# fhd-hdr.net
KiCad netlist of a schematic drawn in EAGLE
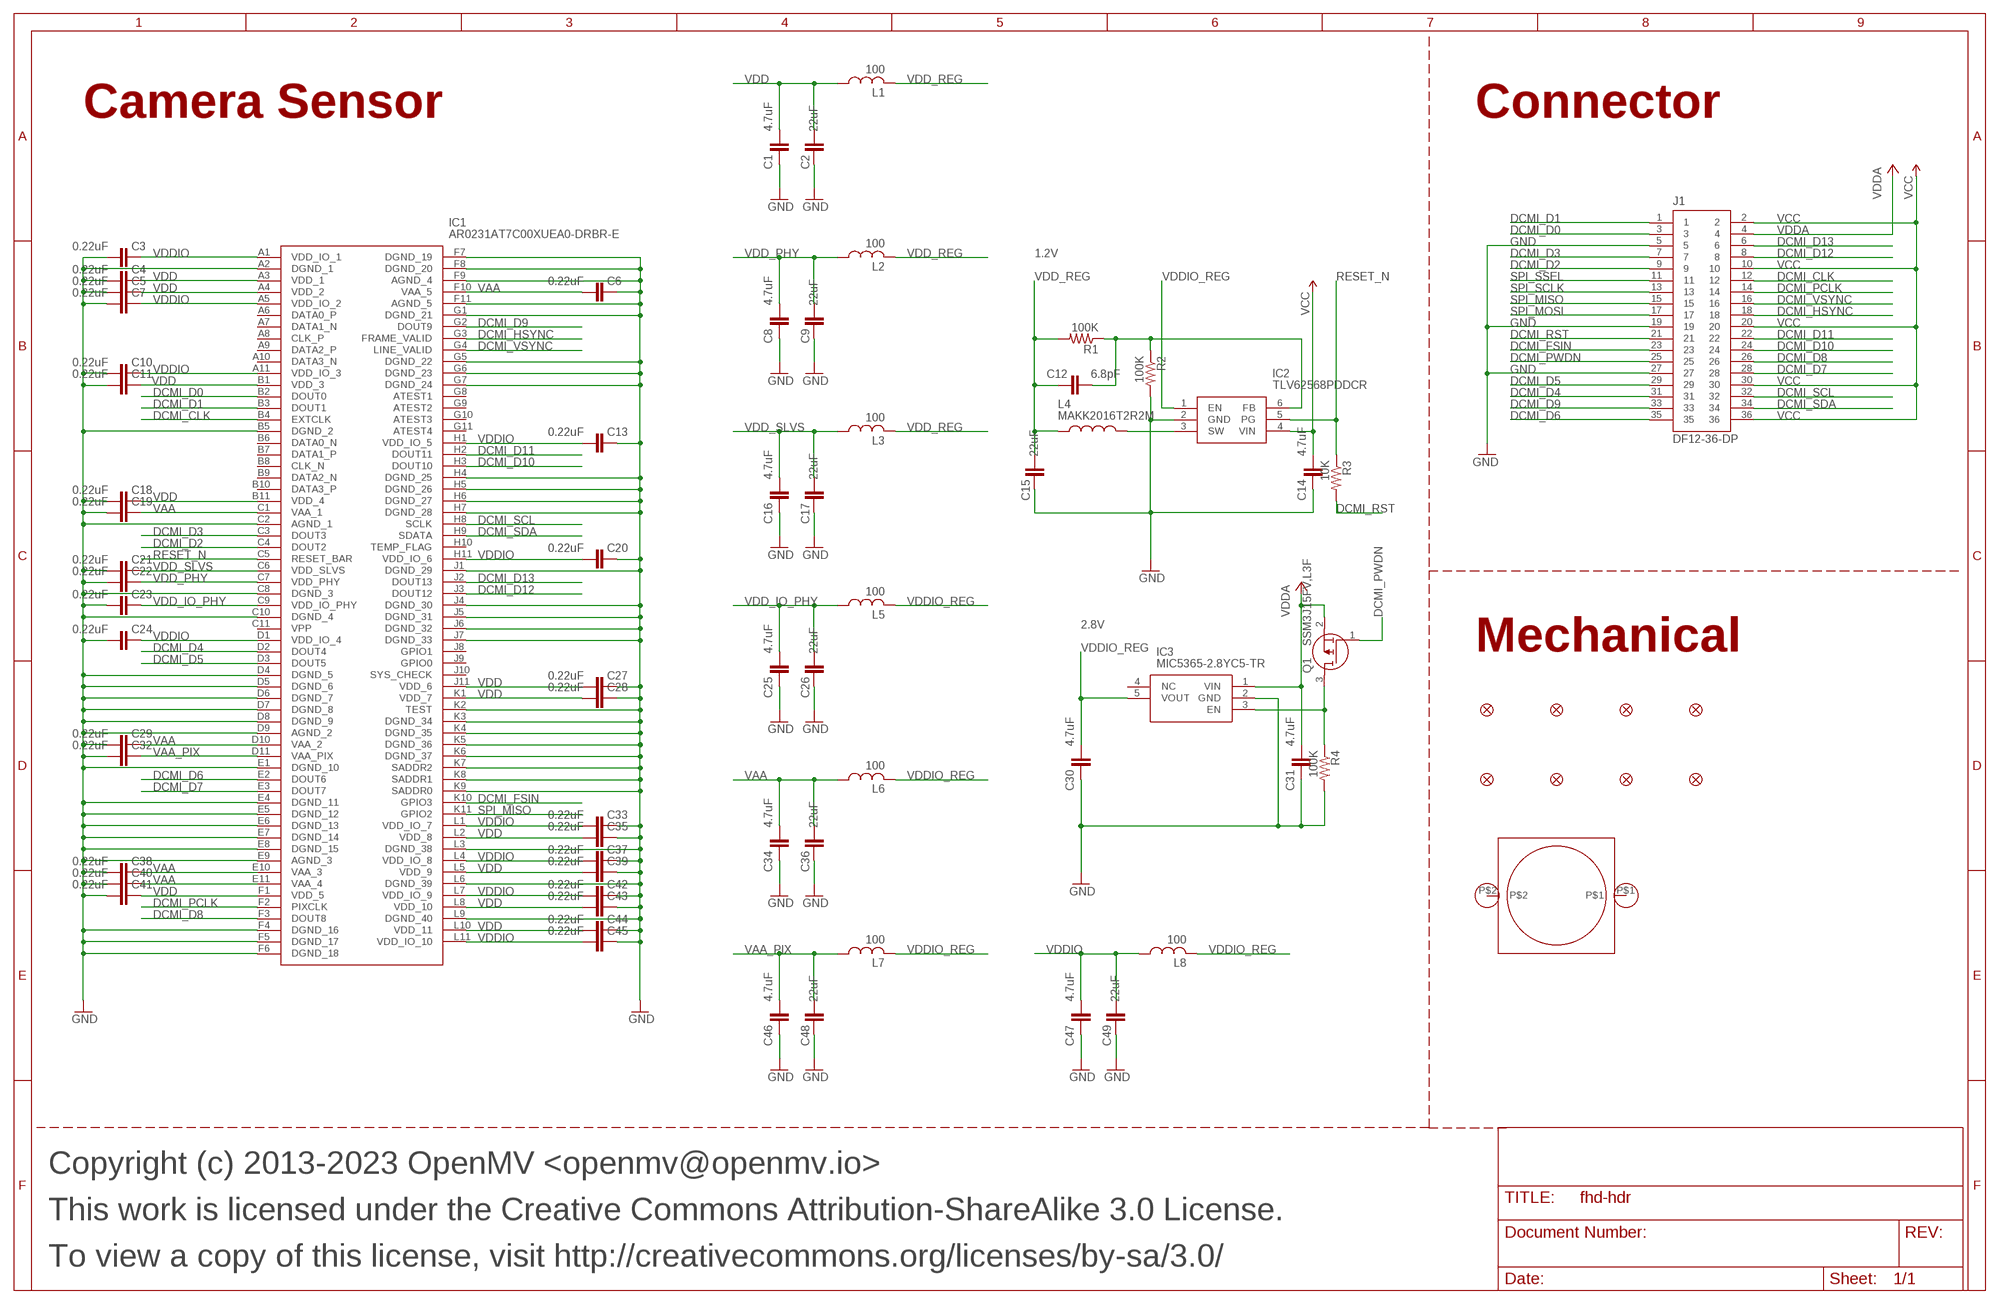
[diagram p0: schematic, sheet 1]

(export (version "E")
  (design (tool "Eeschema 10.0.6"))
  (components
    (comp (ref "C1")
      (value "4.7uF")
      (footprint "eagle-import:0402")
      (fields (field (name "MPN") "JMK105BBJ475MV-F"))
      (libsource (lib "eagle-import") (part "CAP_0402"))
    )
    (comp (ref "C2")
      (value "22uF")
      (footprint "eagle-import:0805")
      (fields (field (name "MPN") "CL21A226MQQNNNE"))
      (libsource (lib "eagle-import") (part "22UF-0805-6.3V-20%"))
    )
    (comp (ref "C3")
      (value "0.22uF")
      (footprint "eagle-import:C0201")
      (fields (field (name "MPN") "GRM033R60J224ME15D"))
      (libsource (lib "eagle-import") (part "C-EUC0201"))
    )
    (comp (ref "C4")
      (value "0.22uF")
      (footprint "eagle-import:C0201")
      (fields (field (name "MPN") "GRM033R60J224ME15D"))
      (libsource (lib "eagle-import") (part "C-EUC0201"))
    )
    (comp (ref "C5")
      (value "0.22uF")
      (footprint "eagle-import:C0201")
      (fields (field (name "MPN") "GRM033R60J224ME15D"))
      (libsource (lib "eagle-import") (part "C-EUC0201"))
    )
    (comp (ref "C6")
      (value "0.22uF")
      (footprint "eagle-import:C0201")
      (fields (field (name "MPN") "GRM033R60J224ME15D"))
      (libsource (lib "eagle-import") (part "C-EUC0201"))
    )
    (comp (ref "C7")
      (value "0.22uF")
      (footprint "eagle-import:C0201")
      (fields (field (name "MPN") "GRM033R60J224ME15D"))
      (libsource (lib "eagle-import") (part "C-EUC0201"))
    )
    (comp (ref "C8")
      (value "4.7uF")
      (footprint "eagle-import:0402")
      (fields (field (name "MPN") "JMK105BBJ475MV-F"))
      (libsource (lib "eagle-import") (part "CAP_0402"))
    )
    (comp (ref "C9")
      (value "22uF")
      (footprint "eagle-import:0805")
      (fields (field (name "MPN") "CL21A226MQQNNNE"))
      (libsource (lib "eagle-import") (part "22UF-0805-6.3V-20%"))
    )
    (comp (ref "C10")
      (value "0.22uF")
      (footprint "eagle-import:C0201")
      (fields (field (name "MPN") "GRM033R60J224ME15D"))
      (libsource (lib "eagle-import") (part "C-EUC0201"))
    )
    (comp (ref "C11")
      (value "0.22uF")
      (footprint "eagle-import:C0201")
      (fields (field (name "MPN") "GRM033R60J224ME15D"))
      (libsource (lib "eagle-import") (part "C-EUC0201"))
    )
    (comp (ref "C12")
      (value "6.8pF")
      (footprint "eagle-import:0402")
      (fields (field (name "MPN") "GRM1555C1H6R8DA01D"))
      (libsource (lib "eagle-import") (part "CAP_0402"))
    )
    (comp (ref "C13")
      (value "0.22uF")
      (footprint "eagle-import:C0201")
      (fields (field (name "MPN") "GRM033R60J224ME15D"))
      (libsource (lib "eagle-import") (part "C-EUC0201"))
    )
    (comp (ref "C14")
      (value "4.7uF")
      (footprint "eagle-import:0402")
      (fields (field (name "MPN") "JMK105BBJ475MV-F"))
      (libsource (lib "eagle-import") (part "CAP_0402"))
    )
    (comp (ref "C15")
      (value "22uF")
      (footprint "eagle-import:0805")
      (fields (field (name "MPN") "CL21A226MQQNNNE"))
      (libsource (lib "eagle-import") (part "22UF-0805-6.3V-20%"))
    )
    (comp (ref "C16")
      (value "4.7uF")
      (footprint "eagle-import:0402")
      (fields (field (name "MPN") "JMK105BBJ475MV-F"))
      (libsource (lib "eagle-import") (part "CAP_0402"))
    )
    (comp (ref "C17")
      (value "22uF")
      (footprint "eagle-import:0805")
      (fields (field (name "MPN") "CL21A226MQQNNNE"))
      (libsource (lib "eagle-import") (part "22UF-0805-6.3V-20%"))
    )
    (comp (ref "C18")
      (value "0.22uF")
      (footprint "eagle-import:C0201")
      (fields (field (name "MPN") "GRM033R60J224ME15D"))
      (libsource (lib "eagle-import") (part "C-EUC0201"))
    )
    (comp (ref "C19")
      (value "0.22uF")
      (footprint "eagle-import:C0201")
      (fields (field (name "MPN") "GRM033R60J224ME15D"))
      (libsource (lib "eagle-import") (part "C-EUC0201"))
    )
    (comp (ref "C20")
      (value "0.22uF")
      (footprint "eagle-import:C0201")
      (fields (field (name "MPN") "GRM033R60J224ME15D"))
      (libsource (lib "eagle-import") (part "C-EUC0201"))
    )
    (comp (ref "C21")
      (value "0.22uF")
      (footprint "eagle-import:C0201")
      (fields (field (name "MPN") "GRM033R60J224ME15D"))
      (libsource (lib "eagle-import") (part "C-EUC0201"))
    )
    (comp (ref "C22")
      (value "0.22uF")
      (footprint "eagle-import:C0201")
      (fields (field (name "MPN") "GRM033R60J224ME15D"))
      (libsource (lib "eagle-import") (part "C-EUC0201"))
    )
    (comp (ref "C23")
      (value "0.22uF")
      (footprint "eagle-import:C0201")
      (fields (field (name "MPN") "GRM033R60J224ME15D"))
      (libsource (lib "eagle-import") (part "C-EUC0201"))
    )
    (comp (ref "C24")
      (value "0.22uF")
      (footprint "eagle-import:C0201")
      (fields (field (name "MPN") "GRM033R60J224ME15D"))
      (libsource (lib "eagle-import") (part "C-EUC0201"))
    )
    (comp (ref "C25")
      (value "4.7uF")
      (footprint "eagle-import:0402")
      (fields (field (name "MPN") "JMK105BBJ475MV-F"))
      (libsource (lib "eagle-import") (part "CAP_0402"))
    )
    (comp (ref "C26")
      (value "22uF")
      (footprint "eagle-import:0805")
      (fields (field (name "MPN") "CL21A226MQQNNNE"))
      (libsource (lib "eagle-import") (part "22UF-0805-6.3V-20%"))
    )
    (comp (ref "C27")
      (value "0.22uF")
      (footprint "eagle-import:C0201")
      (fields (field (name "MPN") "GRM033R60J224ME15D"))
      (libsource (lib "eagle-import") (part "C-EUC0201"))
    )
    (comp (ref "C28")
      (value "0.22uF")
      (footprint "eagle-import:C0201")
      (fields (field (name "MPN") "GRM033R60J224ME15D"))
      (libsource (lib "eagle-import") (part "C-EUC0201"))
    )
    (comp (ref "C29")
      (value "0.22uF")
      (footprint "eagle-import:C0201")
      (fields (field (name "MPN") "GRM033R60J224ME15D"))
      (libsource (lib "eagle-import") (part "C-EUC0201"))
    )
    (comp (ref "C30")
      (value "4.7uF")
      (footprint "eagle-import:0402")
      (fields (field (name "MPN") "JMK105BBJ475MV-F"))
      (libsource (lib "eagle-import") (part "CAP_0402"))
    )
    (comp (ref "C31")
      (value "4.7uF")
      (footprint "eagle-import:0402")
      (fields (field (name "MPN") "JMK105BBJ475MV-F"))
      (libsource (lib "eagle-import") (part "CAP_0402"))
    )
    (comp (ref "C32")
      (value "0.22uF")
      (footprint "eagle-import:C0201")
      (fields (field (name "MPN") "GRM033R60J224ME15D"))
      (libsource (lib "eagle-import") (part "C-EUC0201"))
    )
    (comp (ref "C33")
      (value "0.22uF")
      (footprint "eagle-import:C0201")
      (fields (field (name "MPN") "GRM033R60J224ME15D"))
      (libsource (lib "eagle-import") (part "C-EUC0201"))
    )
    (comp (ref "C34")
      (value "4.7uF")
      (footprint "eagle-import:0402")
      (fields (field (name "MPN") "JMK105BBJ475MV-F"))
      (libsource (lib "eagle-import") (part "CAP_0402"))
    )
    (comp (ref "C35")
      (value "0.22uF")
      (footprint "eagle-import:C0201")
      (fields (field (name "MPN") "GRM033R60J224ME15D"))
      (libsource (lib "eagle-import") (part "C-EUC0201"))
    )
    (comp (ref "C36")
      (value "22uF")
      (footprint "eagle-import:0805")
      (fields (field (name "MPN") "CL21A226MQQNNNE"))
      (libsource (lib "eagle-import") (part "22UF-0805-6.3V-20%"))
    )
    (comp (ref "C37")
      (value "0.22uF")
      (footprint "eagle-import:C0201")
      (fields (field (name "MPN") "GRM033R60J224ME15D"))
      (libsource (lib "eagle-import") (part "C-EUC0201"))
    )
    (comp (ref "C38")
      (value "0.22uF")
      (footprint "eagle-import:C0201")
      (fields (field (name "MPN") "GRM033R60J224ME15D"))
      (libsource (lib "eagle-import") (part "C-EUC0201"))
    )
    (comp (ref "C39")
      (value "0.22uF")
      (footprint "eagle-import:C0201")
      (fields (field (name "MPN") "GRM033R60J224ME15D"))
      (libsource (lib "eagle-import") (part "C-EUC0201"))
    )
    (comp (ref "C40")
      (value "0.22uF")
      (footprint "eagle-import:C0201")
      (fields (field (name "MPN") "GRM033R60J224ME15D"))
      (libsource (lib "eagle-import") (part "C-EUC0201"))
    )
    (comp (ref "C41")
      (value "0.22uF")
      (footprint "eagle-import:C0201")
      (fields (field (name "MPN") "GRM033R60J224ME15D"))
      (libsource (lib "eagle-import") (part "C-EUC0201"))
    )
    (comp (ref "C42")
      (value "0.22uF")
      (footprint "eagle-import:C0201")
      (fields (field (name "MPN") "GRM033R60J224ME15D"))
      (libsource (lib "eagle-import") (part "C-EUC0201"))
    )
    (comp (ref "C43")
      (value "0.22uF")
      (footprint "eagle-import:C0201")
      (fields (field (name "MPN") "GRM033R60J224ME15D"))
      (libsource (lib "eagle-import") (part "C-EUC0201"))
    )
    (comp (ref "C44")
      (value "0.22uF")
      (footprint "eagle-import:C0201")
      (fields (field (name "MPN") "GRM033R60J224ME15D"))
      (libsource (lib "eagle-import") (part "C-EUC0201"))
    )
    (comp (ref "C45")
      (value "0.22uF")
      (footprint "eagle-import:C0201")
      (fields (field (name "MPN") "GRM033R60J224ME15D"))
      (libsource (lib "eagle-import") (part "C-EUC0201"))
    )
    (comp (ref "C46")
      (value "4.7uF")
      (footprint "eagle-import:0402")
      (fields (field (name "MPN") "JMK105BBJ475MV-F"))
      (libsource (lib "eagle-import") (part "CAP_0402"))
    )
    (comp (ref "C47")
      (value "4.7uF")
      (footprint "eagle-import:0402")
      (fields (field (name "MPN") "JMK105BBJ475MV-F"))
      (libsource (lib "eagle-import") (part "CAP_0402"))
    )
    (comp (ref "C48")
      (value "22uF")
      (footprint "eagle-import:0805")
      (fields (field (name "MPN") "CL21A226MQQNNNE"))
      (libsource (lib "eagle-import") (part "22UF-0805-6.3V-20%"))
    )
    (comp (ref "C49")
      (value "22uF")
      (footprint "eagle-import:0805")
      (fields (field (name "MPN") "CL21A226MQQNNNE"))
      (libsource (lib "eagle-import") (part "22UF-0805-6.3V-20%"))
    )
    (comp (ref "FD1")
      (value "FIDUCIAL1X2")
      (footprint "eagle-import:FIDUCIAL-1X2")
      (libsource (lib "eagle-import") (part "FIDUCIAL1X2"))
    )
    (comp (ref "FD2")
      (value "FIDUCIAL1X2")
      (footprint "eagle-import:FIDUCIAL-1X2")
      (libsource (lib "eagle-import") (part "FIDUCIAL1X2"))
    )
    (comp (ref "FD3")
      (value "FIDUCIAL1X2")
      (footprint "eagle-import:FIDUCIAL-1X2")
      (libsource (lib "eagle-import") (part "FIDUCIAL1X2"))
    )
    (comp (ref "FD4")
      (value "FIDUCIAL1X2")
      (footprint "eagle-import:FIDUCIAL-1X2")
      (libsource (lib "eagle-import") (part "FIDUCIAL1X2"))
    )
    (comp (ref "FD5")
      (value "FIDUCIAL1X2")
      (footprint "eagle-import:FIDUCIAL-1X2")
      (libsource (lib "eagle-import") (part "FIDUCIAL1X2"))
    )
    (comp (ref "FD6")
      (value "FIDUCIAL1X2")
      (footprint "eagle-import:FIDUCIAL-1X2")
      (libsource (lib "eagle-import") (part "FIDUCIAL1X2"))
    )
    (comp (ref "FD7")
      (value "FIDUCIAL1X2")
      (footprint "eagle-import:FIDUCIAL-1X2")
      (libsource (lib "eagle-import") (part "FIDUCIAL1X2"))
    )
    (comp (ref "FD8")
      (value "FIDUCIAL1X2")
      (footprint "eagle-import:FIDUCIAL-1X2")
      (libsource (lib "eagle-import") (part "FIDUCIAL1X2"))
    )
    (comp (ref "H1")
      (value "LENSMOUNT20MM")
      (footprint "eagle-import:LENSMOUNT-20MM")
      (libsource (lib "eagle-import") (part "LENSMOUNT20MM"))
    )
    (comp (ref "IC1")
      (value "AR0231AT7C00XUEA0-DRBR-E")
      (footprint "eagle-import:BGA121C80P11X11_1100X1000X155")
      (fields (field (name "MPN") "AR0231AT7C00XUEA0-DPBR"))
      (libsource (lib "eagle-import") (part "AR0231AT7C00XUEA0-DRBR-E"))
    )
    (comp (ref "IC2")
      (value "TLV62568PDDCR")
      (footprint "eagle-import:SOT95P280X110-6N")
      (fields (field (name "MOUSER_PART_NUMBER") "595-TLV62568PDDCR"))
      (libsource (lib "eagle-import") (part "TLV62568PDDCR"))
    )
    (comp (ref "IC3")
      (value "MIC5365-2.8YC5-TR")
      (footprint "eagle-import:SOT65P210X110-5N")
      (fields (field (name "MOUSER_PART_NUMBER") "998-MIC5365-2.8YC5TR"))
      (libsource (lib "eagle-import") (part "MIC5365-2.8YC5-TR"))
    )
    (comp (ref "J1")
      (value "DF12-36-DP")
      (footprint "eagle-import:DF12-36-DP")
      (fields (field (name "MPN") "DF12NB(3.0)-36DP-0.5V(51)"))
      (libsource (lib "eagle-import") (part "DF12-36-DP"))
    )
    (comp (ref "L1")
      (value "100")
      (footprint "eagle-import:0402")
      (fields (field (name "MPN") "MFBM1V1005-101-R"))
      (libsource (lib "eagle-import") (part "INDUCTOR_0402"))
    )
    (comp (ref "L2")
      (value "100")
      (footprint "eagle-import:0402")
      (fields (field (name "MPN") "MFBM1V1005-101-R"))
      (libsource (lib "eagle-import") (part "INDUCTOR_0402"))
    )
    (comp (ref "L3")
      (value "100")
      (footprint "eagle-import:0402")
      (fields (field (name "MPN") "MFBM1V1005-101-R"))
      (libsource (lib "eagle-import") (part "INDUCTOR_0402"))
    )
    (comp (ref "L4")
      (value "MAKK2016T2R2M")
      (footprint "eagle-import:INDC2016X100N")
      (fields (field (name "MF") "Taiyo Yuden"))
      (libsource (lib "eagle-import") (part "MAKK2016T2R2M"))
    )
    (comp (ref "L5")
      (value "100")
      (footprint "eagle-import:0402")
      (fields (field (name "MPN") "MFBM1V1005-101-R"))
      (libsource (lib "eagle-import") (part "INDUCTOR_0402"))
    )
    (comp (ref "L6")
      (value "100")
      (footprint "eagle-import:0402")
      (fields (field (name "MPN") "MFBM1V1005-101-R"))
      (libsource (lib "eagle-import") (part "INDUCTOR_0402"))
    )
    (comp (ref "L7")
      (value "100")
      (footprint "eagle-import:0402")
      (fields (field (name "MPN") "MFBM1V1005-101-R"))
      (libsource (lib "eagle-import") (part "INDUCTOR_0402"))
    )
    (comp (ref "L8")
      (value "100")
      (footprint "eagle-import:0402")
      (fields (field (name "MPN") "MFBM1V1005-101-R"))
      (libsource (lib "eagle-import") (part "INDUCTOR_0402"))
    )
    (comp (ref "Q1")
      (value "SSM3J15FV,L3F")
      (footprint "eagle-import:SSM3J15FVL3F")
      (fields (field (name "MOUSER_PART_NUMBER") "757-SSM3J15FVL3F"))
      (libsource (lib "eagle-import") (part "SSM3J15FV,L3F"))
    )
    (comp (ref "R1")
      (value "100K")
      (footprint "eagle-import:R0402")
      (fields (field (name "MPN") "AC0402FR-07100KL"))
      (libsource (lib "eagle-import") (part "R-US_R0402"))
    )
    (comp (ref "R2")
      (value "100K")
      (footprint "eagle-import:R0402")
      (fields (field (name "MPN") "AC0402FR-07100KL"))
      (libsource (lib "eagle-import") (part "R-US_R0402"))
    )
    (comp (ref "R3")
      (value "10K")
      (footprint "eagle-import:R0402")
      (fields (field (name "MPN") "AC0402FR-1310KL"))
      (libsource (lib "eagle-import") (part "R-US_R0402"))
    )
    (comp (ref "R4")
      (value "100K")
      (footprint "eagle-import:R0402")
      (fields (field (name "MPN") "AC0402FR-07100KL"))
      (libsource (lib "eagle-import") (part "R-US_R0402"))
    )
  )
  (nets
    (net (code "1") (name "/DCMI_CLK") (class "Default")
      (node (ref "IC1") (pin "B4") (pinfunction "EXTCLK_B4") (pintype "bidirectional"))
      (node (ref "J1") (pin "12") (pinfunction "12_12") (pintype "bidirectional"))
    )
    (net (code "2") (name "/DCMI_D0") (class "Default")
      (node (ref "IC1") (pin "B2") (pinfunction "DOUT0_B2") (pintype "bidirectional"))
      (node (ref "J1") (pin "3") (pinfunction "3_3") (pintype "bidirectional"))
    )
    (net (code "3") (name "/DCMI_D1") (class "Default")
      (node (ref "IC1") (pin "B3") (pinfunction "DOUT1_B3") (pintype "bidirectional"))
      (node (ref "J1") (pin "1") (pinfunction "1_1") (pintype "bidirectional"))
    )
    (net (code "4") (name "/DCMI_D2") (class "Default")
      (node (ref "IC1") (pin "C4") (pinfunction "DOUT2_C4") (pintype "bidirectional"))
      (node (ref "J1") (pin "9") (pinfunction "9_9") (pintype "bidirectional"))
    )
    (net (code "5") (name "/DCMI_D3") (class "Default")
      (node (ref "IC1") (pin "C3") (pinfunction "DOUT3_C3") (pintype "bidirectional"))
      (node (ref "J1") (pin "7") (pinfunction "7_7") (pintype "bidirectional"))
    )
    (net (code "6") (name "/DCMI_D4") (class "Default")
      (node (ref "IC1") (pin "D2") (pinfunction "DOUT4_D2") (pintype "bidirectional"))
      (node (ref "J1") (pin "31") (pinfunction "31_31") (pintype "bidirectional"))
    )
    (net (code "7") (name "/DCMI_D5") (class "Default")
      (node (ref "IC1") (pin "D3") (pinfunction "DOUT5_D3") (pintype "bidirectional"))
      (node (ref "J1") (pin "29") (pinfunction "29_29") (pintype "bidirectional"))
    )
    (net (code "8") (name "/DCMI_D6") (class "Default")
      (node (ref "IC1") (pin "E2") (pinfunction "DOUT6_E2") (pintype "bidirectional"))
      (node (ref "J1") (pin "35") (pinfunction "35_35") (pintype "bidirectional"))
    )
    (net (code "9") (name "/DCMI_D7") (class "Default")
      (node (ref "IC1") (pin "E3") (pinfunction "DOUT7_E3") (pintype "bidirectional"))
      (node (ref "J1") (pin "28") (pinfunction "28_28") (pintype "bidirectional"))
    )
    (net (code "10") (name "/DCMI_D8") (class "Default")
      (node (ref "IC1") (pin "F3") (pinfunction "DOUT8_F3") (pintype "bidirectional"))
      (node (ref "J1") (pin "26") (pinfunction "26_26") (pintype "bidirectional"))
    )
    (net (code "11") (name "/DCMI_D9") (class "Default")
      (node (ref "IC1") (pin "G2") (pinfunction "DOUT9_G2") (pintype "bidirectional"))
      (node (ref "J1") (pin "33") (pinfunction "33_33") (pintype "bidirectional"))
    )
    (net (code "12") (name "/DCMI_D10") (class "Default")
      (node (ref "IC1") (pin "H3") (pinfunction "DOUT10_H3") (pintype "bidirectional"))
      (node (ref "J1") (pin "24") (pinfunction "24_24") (pintype "bidirectional"))
    )
    (net (code "13") (name "/DCMI_D11") (class "Default")
      (node (ref "IC1") (pin "H2") (pinfunction "DOUT11_H2") (pintype "bidirectional"))
      (node (ref "J1") (pin "22") (pinfunction "22_22") (pintype "bidirectional"))
    )
    (net (code "14") (name "/DCMI_D12") (class "Default")
      (node (ref "IC1") (pin "J3") (pinfunction "DOUT12_J3") (pintype "bidirectional"))
      (node (ref "J1") (pin "8") (pinfunction "8_8") (pintype "bidirectional"))
    )
    (net (code "15") (name "/DCMI_D13") (class "Default")
      (node (ref "IC1") (pin "J2") (pinfunction "DOUT13_J2") (pintype "bidirectional"))
      (node (ref "J1") (pin "6") (pinfunction "6_6") (pintype "bidirectional"))
    )
    (net (code "16") (name "/DCMI_FSIN") (class "Default")
      (node (ref "IC1") (pin "K10") (pinfunction "GPIO3_K10") (pintype "bidirectional"))
      (node (ref "J1") (pin "23") (pinfunction "23_23") (pintype "bidirectional"))
    )
    (net (code "17") (name "/DCMI_HSYNC") (class "Default")
      (node (ref "IC1") (pin "G3") (pinfunction "FRAME_VALID_G3") (pintype "bidirectional"))
      (node (ref "J1") (pin "18") (pinfunction "18_18") (pintype "bidirectional"))
    )
    (net (code "18") (name "/DCMI_PCLK") (class "Default")
      (node (ref "IC1") (pin "F2") (pinfunction "PIXCLK_F2") (pintype "bidirectional"))
      (node (ref "J1") (pin "14") (pinfunction "14_14") (pintype "bidirectional"))
    )
    (net (code "19") (name "/DCMI_PWDN") (class "Default")
      (node (ref "J1") (pin "25") (pinfunction "25_25") (pintype "bidirectional"))
      (node (ref "Q1") (pin "1") (pinfunction "G_1") (pintype "bidirectional"))
    )
    (net (code "20") (name "/DCMI_RST") (class "Default")
      (node (ref "J1") (pin "21") (pinfunction "21_21") (pintype "bidirectional"))
      (node (ref "R3") (pin "2") (pinfunction "2_2") (pintype "passive"))
    )
    (net (code "21") (name "/DCMI_SCL") (class "Default")
      (node (ref "IC1") (pin "H8") (pinfunction "SCLK_H8") (pintype "bidirectional"))
      (node (ref "J1") (pin "32") (pinfunction "32_32") (pintype "bidirectional"))
    )
    (net (code "22") (name "/DCMI_SDA") (class "Default")
      (node (ref "IC1") (pin "H9") (pinfunction "SDATA_H9") (pintype "bidirectional"))
      (node (ref "J1") (pin "34") (pinfunction "34_34") (pintype "bidirectional"))
    )
    (net (code "23") (name "/DCMI_VSYNC") (class "Default")
      (node (ref "IC1") (pin "G4") (pinfunction "LINE_VALID_G4") (pintype "bidirectional"))
      (node (ref "J1") (pin "16") (pinfunction "16_16") (pintype "bidirectional"))
    )
    (net (code "24") (name "/P$1") (class "Default")
      (node (ref "H1") (pin "P$1") (pinfunction "P$1_P$1") (pintype "power_in"))
    )
    (net (code "25") (name "/P$2") (class "Default")
      (node (ref "H1") (pin "P$2") (pinfunction "P$2_P$2") (pintype "power_in"))
    )
    (net (code "26") (name "/RESET_N") (class "Default")
      (node (ref "IC1") (pin "C5") (pinfunction "RESET_BAR_C5") (pintype "bidirectional"))
      (node (ref "IC2") (pin "5") (pinfunction "PG_5") (pintype "bidirectional"))
      (node (ref "R3") (pin "1") (pinfunction "1_1") (pintype "passive"))
    )
    (net (code "27") (name "/SPI_MISO") (class "Default")
      (node (ref "IC1") (pin "K11") (pinfunction "GPIO2_K11") (pintype "bidirectional"))
      (node (ref "J1") (pin "15") (pinfunction "15_15") (pintype "bidirectional"))
    )
    (net (code "28") (name "/SPI_MOSI") (class "Default")
      (node (ref "J1") (pin "17") (pinfunction "17_17") (pintype "bidirectional"))
    )
    (net (code "29") (name "/SPI_SCLK") (class "Default")
      (node (ref "J1") (pin "13") (pinfunction "13_13") (pintype "bidirectional"))
    )
    (net (code "30") (name "/SPI_SSEL") (class "Default")
      (node (ref "J1") (pin "11") (pinfunction "11_11") (pintype "bidirectional"))
    )
    (net (code "31") (name "/VAA") (class "Default")
      (node (ref "C19") (pin "1") (pinfunction "1_1") (pintype "passive"))
      (node (ref "C29") (pin "1") (pinfunction "1_1") (pintype "passive"))
      (node (ref "C34") (pin "2") (pinfunction "2_2") (pintype "passive"))
      (node (ref "C36") (pin "2") (pinfunction "2_2") (pintype "passive"))
      (node (ref "C38") (pin "1") (pinfunction "1_1") (pintype "passive"))
      (node (ref "C40") (pin "1") (pinfunction "1_1") (pintype "passive"))
      (node (ref "C6") (pin "2") (pinfunction "2_2") (pintype "passive"))
      (node (ref "IC1") (pin "C1") (pinfunction "VAA_1_C1") (pintype "bidirectional"))
      (node (ref "IC1") (pin "D10") (pinfunction "VAA_2_D10") (pintype "bidirectional"))
      (node (ref "IC1") (pin "E10") (pinfunction "VAA_3_E10") (pintype "bidirectional"))
      (node (ref "IC1") (pin "E11") (pinfunction "VAA_4_E11") (pintype "bidirectional"))
      (node (ref "IC1") (pin "F10") (pinfunction "VAA_5_F10") (pintype "bidirectional"))
      (node (ref "L6") (pin "1") (pinfunction "P$1_1") (pintype "passive"))
    )
    (net (code "32") (name "/VAA_PIX") (class "Default")
      (node (ref "C32") (pin "1") (pinfunction "1_1") (pintype "passive"))
      (node (ref "C46") (pin "2") (pinfunction "2_2") (pintype "passive"))
      (node (ref "C48") (pin "2") (pinfunction "2_2") (pintype "passive"))
      (node (ref "IC1") (pin "D11") (pinfunction "VAA_PIX_D11") (pintype "bidirectional"))
      (node (ref "L7") (pin "1") (pinfunction "P$1_1") (pintype "passive"))
    )
    (net (code "33") (name "/VDD") (class "Default")
      (node (ref "C1") (pin "2") (pinfunction "2_2") (pintype "passive"))
      (node (ref "C11") (pin "1") (pinfunction "1_1") (pintype "passive"))
      (node (ref "C18") (pin "1") (pinfunction "1_1") (pintype "passive"))
      (node (ref "C2") (pin "2") (pinfunction "2_2") (pintype "passive"))
      (node (ref "C27") (pin "2") (pinfunction "2_2") (pintype "passive"))
      (node (ref "C28") (pin "2") (pinfunction "2_2") (pintype "passive"))
      (node (ref "C35") (pin "2") (pinfunction "2_2") (pintype "passive"))
      (node (ref "C39") (pin "2") (pinfunction "2_2") (pintype "passive"))
      (node (ref "C4") (pin "1") (pinfunction "1_1") (pintype "passive"))
      (node (ref "C41") (pin "1") (pinfunction "1_1") (pintype "passive"))
      (node (ref "C43") (pin "2") (pinfunction "2_2") (pintype "passive"))
      (node (ref "C44") (pin "2") (pinfunction "2_2") (pintype "passive"))
      (node (ref "C5") (pin "1") (pinfunction "1_1") (pintype "passive"))
      (node (ref "IC1") (pin "A3") (pinfunction "VDD_1_A3") (pintype "bidirectional"))
      (node (ref "IC1") (pin "A4") (pinfunction "VDD_2_A4") (pintype "bidirectional"))
      (node (ref "IC1") (pin "B1") (pinfunction "VDD_3_B1") (pintype "bidirectional"))
      (node (ref "IC1") (pin "B11") (pinfunction "VDD_4_B11") (pintype "bidirectional"))
      (node (ref "IC1") (pin "F1") (pinfunction "VDD_5_F1") (pintype "bidirectional"))
      (node (ref "IC1") (pin "J11") (pinfunction "VDD_6_J11") (pintype "bidirectional"))
      (node (ref "IC1") (pin "K1") (pinfunction "VDD_7_K1") (pintype "bidirectional"))
      (node (ref "IC1") (pin "L10") (pinfunction "VDD_11_L10") (pintype "bidirectional"))
      (node (ref "IC1") (pin "L2") (pinfunction "VDD_8_L2") (pintype "bidirectional"))
      (node (ref "IC1") (pin "L5") (pinfunction "VDD_9_L5") (pintype "bidirectional"))
      (node (ref "IC1") (pin "L8") (pinfunction "VDD_10_L8") (pintype "bidirectional"))
      (node (ref "L1") (pin "1") (pinfunction "P$1_1") (pintype "passive"))
    )
    (net (code "34") (name "/VDDIO") (class "Default")
      (node (ref "C10") (pin "1") (pinfunction "1_1") (pintype "passive"))
      (node (ref "C13") (pin "2") (pinfunction "2_2") (pintype "passive"))
      (node (ref "C20") (pin "2") (pinfunction "2_2") (pintype "passive"))
      (node (ref "C24") (pin "1") (pinfunction "1_1") (pintype "passive"))
      (node (ref "C3") (pin "1") (pinfunction "1_1") (pintype "passive"))
      (node (ref "C33") (pin "2") (pinfunction "2_2") (pintype "passive"))
      (node (ref "C37") (pin "2") (pinfunction "2_2") (pintype "passive"))
      (node (ref "C42") (pin "2") (pinfunction "2_2") (pintype "passive"))
      (node (ref "C45") (pin "2") (pinfunction "2_2") (pintype "passive"))
      (node (ref "C47") (pin "2") (pinfunction "2_2") (pintype "passive"))
      (node (ref "C49") (pin "2") (pinfunction "2_2") (pintype "passive"))
      (node (ref "C7") (pin "1") (pinfunction "1_1") (pintype "passive"))
      (node (ref "IC1") (pin "A1") (pinfunction "VDD_IO_1_A1") (pintype "bidirectional"))
      (node (ref "IC1") (pin "A11") (pinfunction "VDD_IO_3_A11") (pintype "bidirectional"))
      (node (ref "IC1") (pin "A5") (pinfunction "VDD_IO_2_A5") (pintype "bidirectional"))
      (node (ref "IC1") (pin "D1") (pinfunction "VDD_IO_4_D1") (pintype "bidirectional"))
      (node (ref "IC1") (pin "H1") (pinfunction "VDD_IO_5_H1") (pintype "bidirectional"))
      (node (ref "IC1") (pin "H11") (pinfunction "VDD_IO_6_H11") (pintype "bidirectional"))
      (node (ref "IC1") (pin "L1") (pinfunction "VDD_IO_7_L1") (pintype "bidirectional"))
      (node (ref "IC1") (pin "L11") (pinfunction "VDD_IO_10_L11") (pintype "bidirectional"))
      (node (ref "IC1") (pin "L4") (pinfunction "VDD_IO_8_L4") (pintype "bidirectional"))
      (node (ref "IC1") (pin "L7") (pinfunction "VDD_IO_9_L7") (pintype "bidirectional"))
      (node (ref "L8") (pin "1") (pinfunction "P$1_1") (pintype "passive"))
    )
    (net (code "35") (name "/VDDIO_REG") (class "Default")
      (node (ref "C30") (pin "2") (pinfunction "2_2") (pintype "passive"))
      (node (ref "IC2") (pin "1") (pinfunction "EN_1") (pintype "bidirectional"))
      (node (ref "IC3") (pin "5") (pinfunction "VOUT_5") (pintype "bidirectional"))
      (node (ref "L5") (pin "2") (pinfunction "P$2_2") (pintype "passive"))
      (node (ref "L6") (pin "2") (pinfunction "P$2_2") (pintype "passive"))
      (node (ref "L7") (pin "2") (pinfunction "P$2_2") (pintype "passive"))
      (node (ref "L8") (pin "2") (pinfunction "P$2_2") (pintype "passive"))
    )
    (net (code "36") (name "/VDD_IO_PHY") (class "Default")
      (node (ref "C23") (pin "1") (pinfunction "1_1") (pintype "passive"))
      (node (ref "C25") (pin "2") (pinfunction "2_2") (pintype "passive"))
      (node (ref "C26") (pin "2") (pinfunction "2_2") (pintype "passive"))
      (node (ref "IC1") (pin "C9") (pinfunction "VDD_IO_PHY_C9") (pintype "bidirectional"))
      (node (ref "L5") (pin "1") (pinfunction "P$1_1") (pintype "passive"))
    )
    (net (code "37") (name "/VDD_PHY") (class "Default")
      (node (ref "C22") (pin "1") (pinfunction "1_1") (pintype "passive"))
      (node (ref "C8") (pin "2") (pinfunction "2_2") (pintype "passive"))
      (node (ref "C9") (pin "2") (pinfunction "2_2") (pintype "passive"))
      (node (ref "IC1") (pin "C7") (pinfunction "VDD_PHY_C7") (pintype "bidirectional"))
      (node (ref "L2") (pin "1") (pinfunction "P$1_1") (pintype "passive"))
    )
    (net (code "38") (name "/VDD_REG") (class "Default")
      (node (ref "C12") (pin "1") (pinfunction "1_1") (pintype "passive"))
      (node (ref "C15") (pin "2") (pinfunction "2_2") (pintype "passive"))
      (node (ref "L1") (pin "2") (pinfunction "P$2_2") (pintype "passive"))
      (node (ref "L2") (pin "2") (pinfunction "P$2_2") (pintype "passive"))
      (node (ref "L3") (pin "2") (pinfunction "P$2_2") (pintype "passive"))
      (node (ref "L4") (pin "1") (pinfunction "1_1") (pintype "passive"))
      (node (ref "R1") (pin "2") (pinfunction "2_2") (pintype "passive"))
    )
    (net (code "39") (name "/VDD_SLVS") (class "Default")
      (node (ref "C16") (pin "2") (pinfunction "2_2") (pintype "passive"))
      (node (ref "C17") (pin "2") (pinfunction "2_2") (pintype "passive"))
      (node (ref "C21") (pin "1") (pinfunction "1_1") (pintype "passive"))
      (node (ref "IC1") (pin "C6") (pinfunction "VDD_SLVS_C6") (pintype "bidirectional"))
      (node (ref "L3") (pin "1") (pinfunction "P$1_1") (pintype "passive"))
    )
    (net (code "40") (name "GND") (class "Default")
      (node (ref "C1") (pin "1") (pinfunction "1_1") (pintype "passive"))
      (node (ref "C10") (pin "2") (pinfunction "2_2") (pintype "passive"))
      (node (ref "C11") (pin "2") (pinfunction "2_2") (pintype "passive"))
      (node (ref "C13") (pin "1") (pinfunction "1_1") (pintype "passive"))
      (node (ref "C14") (pin "1") (pinfunction "1_1") (pintype "passive"))
      (node (ref "C15") (pin "1") (pinfunction "1_1") (pintype "passive"))
      (node (ref "C16") (pin "1") (pinfunction "1_1") (pintype "passive"))
      (node (ref "C17") (pin "1") (pinfunction "1_1") (pintype "passive"))
      (node (ref "C18") (pin "2") (pinfunction "2_2") (pintype "passive"))
      (node (ref "C19") (pin "2") (pinfunction "2_2") (pintype "passive"))
      (node (ref "C2") (pin "1") (pinfunction "1_1") (pintype "passive"))
      (node (ref "C20") (pin "1") (pinfunction "1_1") (pintype "passive"))
      (node (ref "C21") (pin "2") (pinfunction "2_2") (pintype "passive"))
      (node (ref "C22") (pin "2") (pinfunction "2_2") (pintype "passive"))
      (node (ref "C23") (pin "2") (pinfunction "2_2") (pintype "passive"))
      (node (ref "C24") (pin "2") (pinfunction "2_2") (pintype "passive"))
      (node (ref "C25") (pin "1") (pinfunction "1_1") (pintype "passive"))
      (node (ref "C26") (pin "1") (pinfunction "1_1") (pintype "passive"))
      (node (ref "C27") (pin "1") (pinfunction "1_1") (pintype "passive"))
      (node (ref "C28") (pin "1") (pinfunction "1_1") (pintype "passive"))
      (node (ref "C29") (pin "2") (pinfunction "2_2") (pintype "passive"))
      (node (ref "C3") (pin "2") (pinfunction "2_2") (pintype "passive"))
      (node (ref "C30") (pin "1") (pinfunction "1_1") (pintype "passive"))
      (node (ref "C31") (pin "1") (pinfunction "1_1") (pintype "passive"))
      (node (ref "C32") (pin "2") (pinfunction "2_2") (pintype "passive"))
      (node (ref "C33") (pin "1") (pinfunction "1_1") (pintype "passive"))
      (node (ref "C34") (pin "1") (pinfunction "1_1") (pintype "passive"))
      (node (ref "C35") (pin "1") (pinfunction "1_1") (pintype "passive"))
      (node (ref "C36") (pin "1") (pinfunction "1_1") (pintype "passive"))
      (node (ref "C37") (pin "1") (pinfunction "1_1") (pintype "passive"))
      (node (ref "C38") (pin "2") (pinfunction "2_2") (pintype "passive"))
      (node (ref "C39") (pin "1") (pinfunction "1_1") (pintype "passive"))
      (node (ref "C4") (pin "2") (pinfunction "2_2") (pintype "passive"))
      (node (ref "C40") (pin "2") (pinfunction "2_2") (pintype "passive"))
      (node (ref "C41") (pin "2") (pinfunction "2_2") (pintype "passive"))
      (node (ref "C42") (pin "1") (pinfunction "1_1") (pintype "passive"))
      (node (ref "C43") (pin "1") (pinfunction "1_1") (pintype "passive"))
      (node (ref "C44") (pin "1") (pinfunction "1_1") (pintype "passive"))
      (node (ref "C45") (pin "1") (pinfunction "1_1") (pintype "passive"))
      (node (ref "C46") (pin "1") (pinfunction "1_1") (pintype "passive"))
      (node (ref "C47") (pin "1") (pinfunction "1_1") (pintype "passive"))
      (node (ref "C48") (pin "1") (pinfunction "1_1") (pintype "passive"))
      (node (ref "C49") (pin "1") (pinfunction "1_1") (pintype "passive"))
      (node (ref "C5") (pin "2") (pinfunction "2_2") (pintype "passive"))
      (node (ref "C6") (pin "1") (pinfunction "1_1") (pintype "passive"))
      (node (ref "C7") (pin "2") (pinfunction "2_2") (pintype "passive"))
      (node (ref "C8") (pin "1") (pinfunction "1_1") (pintype "passive"))
      (node (ref "C9") (pin "1") (pinfunction "1_1") (pintype "passive"))
      (node (ref "IC1") (pin "A2") (pinfunction "DGND_1_A2") (pintype "bidirectional"))
      (node (ref "IC1") (pin "B5") (pinfunction "DGND_2_B5") (pintype "bidirectional"))
      (node (ref "IC1") (pin "C10") (pinfunction "DGND_4_C10") (pintype "bidirectional"))
      (node (ref "IC1") (pin "C2") (pinfunction "AGND_1_C2") (pintype "bidirectional"))
      (node (ref "IC1") (pin "C8") (pinfunction "DGND_3_C8") (pintype "bidirectional"))
      (node (ref "IC1") (pin "D4") (pinfunction "DGND_5_D4") (pintype "bidirectional"))
      (node (ref "IC1") (pin "D5") (pinfunction "DGND_6_D5") (pintype "bidirectional"))
      (node (ref "IC1") (pin "D6") (pinfunction "DGND_7_D6") (pintype "bidirectional"))
      (node (ref "IC1") (pin "D7") (pinfunction "DGND_8_D7") (pintype "bidirectional"))
      (node (ref "IC1") (pin "D8") (pinfunction "DGND_9_D8") (pintype "bidirectional"))
      (node (ref "IC1") (pin "D9") (pinfunction "AGND_2_D9") (pintype "bidirectional"))
      (node (ref "IC1") (pin "E1") (pinfunction "DGND_10_E1") (pintype "bidirectional"))
      (node (ref "IC1") (pin "E4") (pinfunction "DGND_11_E4") (pintype "bidirectional"))
      (node (ref "IC1") (pin "E5") (pinfunction "DGND_12_E5") (pintype "bidirectional"))
      (node (ref "IC1") (pin "E6") (pinfunction "DGND_13_E6") (pintype "bidirectional"))
      (node (ref "IC1") (pin "E7") (pinfunction "DGND_14_E7") (pintype "bidirectional"))
      (node (ref "IC1") (pin "E8") (pinfunction "DGND_15_E8") (pintype "bidirectional"))
      (node (ref "IC1") (pin "E9") (pinfunction "AGND_3_E9") (pintype "bidirectional"))
      (node (ref "IC1") (pin "F11") (pinfunction "AGND_5_F11") (pintype "bidirectional"))
      (node (ref "IC1") (pin "F4") (pinfunction "DGND_16_F4") (pintype "bidirectional"))
      (node (ref "IC1") (pin "F5") (pinfunction "DGND_17_F5") (pintype "bidirectional"))
      (node (ref "IC1") (pin "F6") (pinfunction "DGND_18_F6") (pintype "bidirectional"))
      (node (ref "IC1") (pin "F7") (pinfunction "DGND_19_F7") (pintype "bidirectional"))
      (node (ref "IC1") (pin "F8") (pinfunction "DGND_20_F8") (pintype "bidirectional"))
      (node (ref "IC1") (pin "F9") (pinfunction "AGND_4_F9") (pintype "bidirectional"))
      (node (ref "IC1") (pin "G1") (pinfunction "DGND_21_G1") (pintype "bidirectional"))
      (node (ref "IC1") (pin "G5") (pinfunction "DGND_22_G5") (pintype "bidirectional"))
      (node (ref "IC1") (pin "G6") (pinfunction "DGND_23_G6") (pintype "bidirectional"))
      (node (ref "IC1") (pin "G7") (pinfunction "DGND_24_G7") (pintype "bidirectional"))
      (node (ref "IC1") (pin "H4") (pinfunction "DGND_25_H4") (pintype "bidirectional"))
      (node (ref "IC1") (pin "H5") (pinfunction "DGND_26_H5") (pintype "bidirectional"))
      (node (ref "IC1") (pin "H6") (pinfunction "DGND_27_H6") (pintype "bidirectional"))
      (node (ref "IC1") (pin "H7") (pinfunction "DGND_28_H7") (pintype "bidirectional"))
      (node (ref "IC1") (pin "J1") (pinfunction "DGND_29_J1") (pintype "bidirectional"))
      (node (ref "IC1") (pin "J4") (pinfunction "DGND_30_J4") (pintype "bidirectional"))
      (node (ref "IC1") (pin "J5") (pinfunction "DGND_31_J5") (pintype "bidirectional"))
      (node (ref "IC1") (pin "J6") (pinfunction "DGND_32_J6") (pintype "bidirectional"))
      (node (ref "IC1") (pin "J7") (pinfunction "DGND_33_J7") (pintype "bidirectional"))
      (node (ref "IC1") (pin "K2") (pinfunction "TEST_K2") (pintype "bidirectional"))
      (node (ref "IC1") (pin "K3") (pinfunction "DGND_34_K3") (pintype "bidirectional"))
      (node (ref "IC1") (pin "K4") (pinfunction "DGND_35_K4") (pintype "bidirectional"))
      (node (ref "IC1") (pin "K5") (pinfunction "DGND_36_K5") (pintype "bidirectional"))
      (node (ref "IC1") (pin "K6") (pinfunction "DGND_37_K6") (pintype "bidirectional"))
      (node (ref "IC1") (pin "K7") (pinfunction "SADDR2_K7") (pintype "bidirectional"))
      (node (ref "IC1") (pin "K8") (pinfunction "SADDR1_K8") (pintype "bidirectional"))
      (node (ref "IC1") (pin "K9") (pinfunction "SADDR0_K9") (pintype "bidirectional"))
      (node (ref "IC1") (pin "L3") (pinfunction "DGND_38_L3") (pintype "bidirectional"))
      (node (ref "IC1") (pin "L6") (pinfunction "DGND_39_L6") (pintype "bidirectional"))
      (node (ref "IC1") (pin "L9") (pinfunction "DGND_40_L9") (pintype "bidirectional"))
      (node (ref "IC2") (pin "2") (pinfunction "GND_2") (pintype "bidirectional"))
      (node (ref "IC3") (pin "2") (pinfunction "GND_2") (pintype "bidirectional"))
      (node (ref "J1") (pin "19") (pinfunction "19_19") (pintype "bidirectional"))
      (node (ref "J1") (pin "27") (pinfunction "27_27") (pintype "bidirectional"))
      (node (ref "J1") (pin "5") (pinfunction "5_5") (pintype "bidirectional"))
      (node (ref "R2") (pin "2") (pinfunction "2_2") (pintype "passive"))
      (node (ref "R4") (pin "2") (pinfunction "2_2") (pintype "passive"))
    )
    (net (code "41") (name "Net-(IC2-FB)") (class "Default")
      (node (ref "C12") (pin "2") (pinfunction "2_2") (pintype "passive"))
      (node (ref "IC2") (pin "6") (pinfunction "FB_6") (pintype "bidirectional"))
      (node (ref "R1") (pin "1") (pinfunction "1_1") (pintype "passive"))
      (node (ref "R2") (pin "1") (pinfunction "1_1") (pintype "passive"))
    )
    (net (code "42") (name "Net-(IC2-SW)") (class "Default")
      (node (ref "IC2") (pin "3") (pinfunction "SW_3") (pintype "bidirectional"))
      (node (ref "L4") (pin "2") (pinfunction "2_2") (pintype "passive"))
    )
    (net (code "43") (name "Net-(IC3-EN)") (class "Default")
      (node (ref "IC3") (pin "3") (pinfunction "EN_3") (pintype "bidirectional"))
      (node (ref "Q1") (pin "3") (pinfunction "D_3") (pintype "bidirectional"))
      (node (ref "R4") (pin "1") (pinfunction "1_1") (pintype "passive"))
    )
    (net (code "44") (name "VCC") (class "Default")
      (node (ref "C14") (pin "2") (pinfunction "2_2") (pintype "passive"))
      (node (ref "IC2") (pin "4") (pinfunction "VIN_4") (pintype "bidirectional"))
      (node (ref "J1") (pin "10") (pinfunction "10_10") (pintype "bidirectional"))
      (node (ref "J1") (pin "2") (pinfunction "2_2") (pintype "bidirectional"))
      (node (ref "J1") (pin "20") (pinfunction "20_20") (pintype "bidirectional"))
      (node (ref "J1") (pin "30") (pinfunction "30_30") (pintype "bidirectional"))
      (node (ref "J1") (pin "36") (pinfunction "36_36") (pintype "bidirectional"))
    )
    (net (code "45") (name "VDDA") (class "Default")
      (node (ref "C31") (pin "2") (pinfunction "2_2") (pintype "passive"))
      (node (ref "IC3") (pin "1") (pinfunction "VIN_1") (pintype "bidirectional"))
      (node (ref "J1") (pin "4") (pinfunction "4_4") (pintype "bidirectional"))
      (node (ref "Q1") (pin "2") (pinfunction "S_2") (pintype "bidirectional"))
    )
    (net (code "46") (name "unconnected-(IC1-ATEST1-PadG8)") (class "Default")
      (node (ref "IC1") (pin "G8") (pinfunction "ATEST1_G8") (pintype "bidirectional"))
    )
    (net (code "47") (name "unconnected-(IC1-ATEST2-PadG9)") (class "Default")
      (node (ref "IC1") (pin "G9") (pinfunction "ATEST2_G9") (pintype "bidirectional"))
    )
    (net (code "48") (name "unconnected-(IC1-ATEST3-PadG10)") (class "Default")
      (node (ref "IC1") (pin "G10") (pinfunction "ATEST3_G10") (pintype "bidirectional"))
    )
    (net (code "49") (name "unconnected-(IC1-ATEST4-PadG11)") (class "Default")
      (node (ref "IC1") (pin "G11") (pinfunction "ATEST4_G11") (pintype "bidirectional"))
    )
    (net (code "50") (name "unconnected-(IC1-CLK_N-PadB8)") (class "Default")
      (node (ref "IC1") (pin "B8") (pinfunction "CLK_N_B8") (pintype "bidirectional"))
    )
    (net (code "51") (name "unconnected-(IC1-CLK_P-PadA8)") (class "Default")
      (node (ref "IC1") (pin "A8") (pinfunction "CLK_P_A8") (pintype "bidirectional"))
    )
    (net (code "52") (name "unconnected-(IC1-DATA0_N-PadB6)") (class "Default")
      (node (ref "IC1") (pin "B6") (pinfunction "DATA0_N_B6") (pintype "bidirectional"))
    )
    (net (code "53") (name "unconnected-(IC1-DATA0_P-PadA6)") (class "Default")
      (node (ref "IC1") (pin "A6") (pinfunction "DATA0_P_A6") (pintype "bidirectional"))
    )
    (net (code "54") (name "unconnected-(IC1-DATA1_N-PadA7)") (class "Default")
      (node (ref "IC1") (pin "A7") (pinfunction "DATA1_N_A7") (pintype "bidirectional"))
    )
    (net (code "55") (name "unconnected-(IC1-DATA1_P-PadB7)") (class "Default")
      (node (ref "IC1") (pin "B7") (pinfunction "DATA1_P_B7") (pintype "bidirectional"))
    )
    (net (code "56") (name "unconnected-(IC1-DATA2_N-PadB9)") (class "Default")
      (node (ref "IC1") (pin "B9") (pinfunction "DATA2_N_B9") (pintype "bidirectional"))
    )
    (net (code "57") (name "unconnected-(IC1-DATA2_P-PadA9)") (class "Default")
      (node (ref "IC1") (pin "A9") (pinfunction "DATA2_P_A9") (pintype "bidirectional"))
    )
    (net (code "58") (name "unconnected-(IC1-DATA3_N-PadA10)") (class "Default")
      (node (ref "IC1") (pin "A10") (pinfunction "DATA3_N_A10") (pintype "bidirectional"))
    )
    (net (code "59") (name "unconnected-(IC1-DATA3_P-PadB10)") (class "Default")
      (node (ref "IC1") (pin "B10") (pinfunction "DATA3_P_B10") (pintype "bidirectional"))
    )
    (net (code "60") (name "unconnected-(IC1-GPIO0-PadJ9)") (class "Default")
      (node (ref "IC1") (pin "J9") (pinfunction "GPIO0_J9") (pintype "bidirectional"))
    )
    (net (code "61") (name "unconnected-(IC1-GPIO1-PadJ8)") (class "Default")
      (node (ref "IC1") (pin "J8") (pinfunction "GPIO1_J8") (pintype "bidirectional"))
    )
    (net (code "62") (name "unconnected-(IC1-SYS_CHECK-PadJ10)") (class "Default")
      (node (ref "IC1") (pin "J10") (pinfunction "SYS_CHECK_J10") (pintype "bidirectional"))
    )
    (net (code "63") (name "unconnected-(IC1-TEMP_FLAG-PadH10)") (class "Default")
      (node (ref "IC1") (pin "H10") (pinfunction "TEMP_FLAG_H10") (pintype "bidirectional"))
    )
    (net (code "64") (name "unconnected-(IC1-VPP-PadC11)") (class "Default")
      (node (ref "IC1") (pin "C11") (pinfunction "VPP_C11") (pintype "bidirectional"))
    )
    (net (code "65") (name "unconnected-(IC3-NC-Pad4)") (class "Default")
      (node (ref "IC3") (pin "4") (pinfunction "NC_4") (pintype "no_connect"))
    )
  )
)
